# AFE.net
KiCad netlist of a schematic drawn in Altium Designer
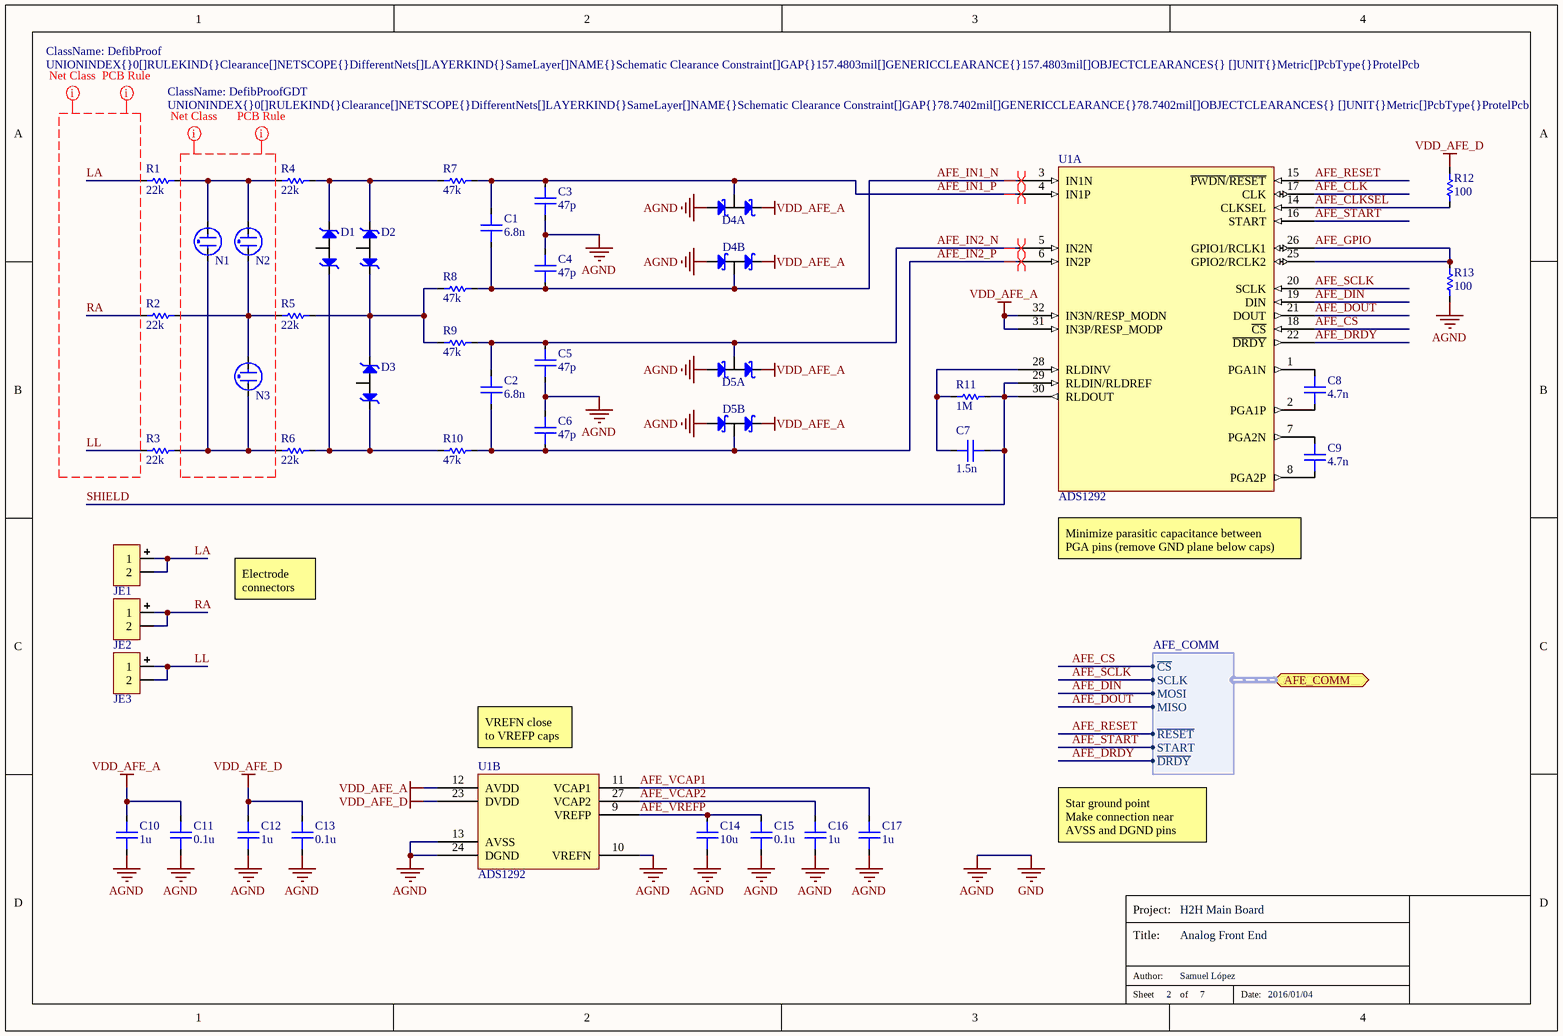
[diagram p0: AFE.SchDoc]

(export (version "E")
  (design (tool "Eeschema 10.0.6"))
  (components
    (comp (ref "C1")
      (value "6.8n")
      (footprint "C0603")
      (description "Capacitor")
      (libsource (lib "Misc") (part "Capacitor"))
    )
    (comp (ref "C2")
      (value "6.8n")
      (footprint "C0603")
      (description "Capacitor")
      (libsource (lib "Misc") (part "Capacitor"))
    )
    (comp (ref "C3")
      (value "47p")
      (footprint "C0603")
      (description "Capacitor")
      (libsource (lib "Misc") (part "Capacitor"))
    )
    (comp (ref "C4")
      (value "47p")
      (footprint "C0603")
      (description "Capacitor")
      (libsource (lib "Misc") (part "Capacitor"))
    )
    (comp (ref "C5")
      (value "47p")
      (footprint "C0603")
      (description "Capacitor")
      (libsource (lib "Misc") (part "Capacitor"))
    )
    (comp (ref "C6")
      (value "47p")
      (footprint "C0603")
      (description "Capacitor")
      (libsource (lib "Misc") (part "Capacitor"))
    )
    (comp (ref "C7")
      (value "1.5n")
      (footprint "C0603")
      (description "Capacitor")
      (libsource (lib "Misc") (part "Capacitor"))
    )
    (comp (ref "C8")
      (value "4.7n")
      (footprint "C0603")
      (description "Capacitor")
      (libsource (lib "Misc") (part "Capacitor"))
    )
    (comp (ref "C9")
      (value "4.7n")
      (footprint "C0603")
      (description "Capacitor")
      (libsource (lib "Misc") (part "Capacitor"))
    )
    (comp (ref "C10")
      (value "1u")
      (footprint "C0603")
      (description "Capacitor")
      (libsource (lib "Misc") (part "Capacitor"))
    )
    (comp (ref "C11")
      (value "0.1u")
      (footprint "C0603")
      (description "Capacitor")
      (libsource (lib "Misc") (part "Capacitor"))
    )
    (comp (ref "C12")
      (value "1u")
      (footprint "C0603")
      (description "Capacitor")
      (libsource (lib "Misc") (part "Capacitor"))
    )
    (comp (ref "C13")
      (value "0.1u")
      (footprint "C0603")
      (description "Capacitor")
      (libsource (lib "Misc") (part "Capacitor"))
    )
    (comp (ref "C14")
      (value "10u")
      (footprint "C0603")
      (description "Capacitor")
      (libsource (lib "Misc") (part "Capacitor"))
    )
    (comp (ref "C15")
      (value "0.1u")
      (footprint "C0603")
      (description "Capacitor")
      (libsource (lib "Misc") (part "Capacitor"))
    )
    (comp (ref "C16")
      (value "1u")
      (footprint "C0603")
      (description "Capacitor")
      (libsource (lib "Misc") (part "Capacitor"))
    )
    (comp (ref "C17")
      (value "1u")
      (footprint "C0603")
      (description "Capacitor")
      (libsource (lib "Misc") (part "Capacitor"))
    )
    (comp (ref "D1")
      (value "PESD5V0X1")
      (footprint "PESD5V0X1BT")
      (description "TVS - Bidirectional Zener Diode")
      (libsource (lib "H2H") (part "PESD5V0X1"))
    )
    (comp (ref "D2")
      (value "PESD5V0X1")
      (footprint "PESD5V0X1BT")
      (description "TVS - Bidirectional Zener Diode")
      (libsource (lib "H2H") (part "PESD5V0X1"))
    )
    (comp (ref "D3")
      (value "PESD5V0X1")
      (footprint "PESD5V0X1BT")
      (description "TVS - Bidirectional Zener Diode")
      (libsource (lib "H2H") (part "PESD5V0X1"))
    )
    (comp (ref "D4")
      (value "BAS70DW-04")
      (footprint "BAS70DW-04")
      (description "TVS - Dual Schottky Rail-to-rail Protection")
      (libsource (lib "H2H") (part "BAS70DW-04"))
    )
    (comp (ref "D5")
      (value "BAS70DW-04")
      (footprint "BAS70DW-04")
      (description "TVS - Dual Schottky Rail-to-rail Protection")
      (libsource (lib "H2H") (part "BAS70DW-04"))
    )
    (comp (ref "JE1")
      (value "JST PH 2 Pin")
      (footprint "S2B-PH-K-S")
      (description "Conn - Battery, Male, 2 Pin, PCB, Right Angle")
      (libsource (lib "Conn") (part "S2B-PH-K-S"))
    )
    (comp (ref "JE2")
      (value "JST PH 2 Pin")
      (footprint "S2B-PH-K-S")
      (description "Conn - Battery, Male, 2 Pin, PCB, Right Angle")
      (libsource (lib "Conn") (part "S2B-PH-K-S"))
    )
    (comp (ref "JE3")
      (value "JST PH 2 Pin")
      (footprint "S2B-PH-K-S")
      (description "Conn - Battery, Male, 2 Pin, PCB, Right Angle")
      (libsource (lib "Conn") (part "S2B-PH-K-S"))
    )
    (comp (ref "N1")
      (value "GDT")
      (footprint "2051-09-SM")
      (description "TVS - Gas Discharge Tube")
      (libsource (lib "H2H") (part "2051-09-SM"))
    )
    (comp (ref "N2")
      (value "GDT")
      (footprint "2051-09-SM")
      (description "TVS - Gas Discharge Tube")
      (libsource (lib "H2H") (part "2051-09-SM"))
    )
    (comp (ref "N3")
      (value "GDT")
      (footprint "2051-09-SM")
      (description "TVS - Gas Discharge Tube")
      (libsource (lib "H2H") (part "2051-09-SM"))
    )
    (comp (ref "R1")
      (value "22k")
      (footprint "R2512")
      (description "Resistor")
      (libsource (lib "Misc") (part "Resistor"))
    )
    (comp (ref "R2")
      (value "22k")
      (footprint "R2512")
      (description "Resistor")
      (libsource (lib "Misc") (part "Resistor"))
    )
    (comp (ref "R3")
      (value "22k")
      (footprint "R2512")
      (description "Resistor")
      (libsource (lib "Misc") (part "Resistor"))
    )
    (comp (ref "R4")
      (value "22k")
      (footprint "R2512")
      (description "Resistor")
      (libsource (lib "Misc") (part "Resistor"))
    )
    (comp (ref "R5")
      (value "22k")
      (footprint "R2512")
      (description "Resistor")
      (libsource (lib "Misc") (part "Resistor"))
    )
    (comp (ref "R6")
      (value "22k")
      (footprint "R2512")
      (description "Resistor")
      (libsource (lib "Misc") (part "Resistor"))
    )
    (comp (ref "R7")
      (value "47k")
      (footprint "R0603")
      (description "Resistor")
      (libsource (lib "Misc") (part "Resistor"))
    )
    (comp (ref "R8")
      (value "47k")
      (footprint "R0603")
      (description "Resistor")
      (libsource (lib "Misc") (part "Resistor"))
    )
    (comp (ref "R9")
      (value "47k")
      (footprint "R0603")
      (description "Resistor")
      (libsource (lib "Misc") (part "Resistor"))
    )
    (comp (ref "R10")
      (value "47k")
      (footprint "R0603")
      (description "Resistor")
      (libsource (lib "Misc") (part "Resistor"))
    )
    (comp (ref "R11")
      (value "1M")
      (footprint "R0603")
      (description "Resistor")
      (libsource (lib "Misc") (part "Resistor"))
    )
    (comp (ref "R12")
      (value "100")
      (footprint "R0603")
      (description "Resistor")
      (libsource (lib "Misc") (part "Resistor"))
    )
    (comp (ref "R13")
      (value "100")
      (footprint "R0603")
      (description "Resistor")
      (libsource (lib "Misc") (part "Resistor"))
    )
    (comp (ref "U1")
      (value "ADS1292")
      (footprint "ADS129x")
      (description "IC - Analog Front End - Medical")
      (libsource (lib "H2H") (part "ADS1292"))
    )
  )
  (nets
    (net (code "2") (name "/AFE_CLK") (class "Default")
      (node (ref "U1") (pin "17") (pinfunction "CLK_17") (pintype "bidirectional"))
    )
    (net (code "3") (name "/AFE_CLKSEL") (class "Default")
      (node (ref "R12") (pin "2") (pinfunction "2_2") (pintype "passive"))
      (node (ref "U1") (pin "14") (pinfunction "CLKSEL_14") (pintype "input"))
    )
    (net (code "4") (name "/AFE_CS") (class "Default")
      (node (ref "U1") (pin "18") (pinfunction "~{CS}_18") (pintype "input"))
    )
    (net (code "5") (name "/AFE_DIN") (class "Default")
      (node (ref "U1") (pin "19") (pinfunction "DIN_19") (pintype "input"))
    )
    (net (code "6") (name "/AFE_DOUT") (class "Default")
      (node (ref "U1") (pin "21") (pinfunction "DOUT_21") (pintype "output"))
    )
    (net (code "7") (name "/AFE_DRDY") (class "Default")
      (node (ref "U1") (pin "22") (pinfunction "~{DRDY}_22") (pintype "output"))
    )
    (net (code "8") (name "/AFE_GPIO") (class "Default")
      (node (ref "R13") (pin "1") (pinfunction "1_1") (pintype "passive"))
      (node (ref "U1") (pin "25") (pinfunction "GPIO2/RCLK2_25") (pintype "bidirectional"))
      (node (ref "U1") (pin "26") (pinfunction "GPIO1/RCLK1_26") (pintype "bidirectional"))
    )
    (net (code "9") (name "/AFE_IN1_N") (class "Default")
      (node (ref "C1") (pin "1") (pinfunction "1_1") (pintype "passive"))
      (node (ref "C4") (pin "1") (pinfunction "1_1") (pintype "passive"))
      (node (ref "D4") (pin "3") (pinfunction "AK2_3") (pintype "passive"))
      (node (ref "R8") (pin "2") (pinfunction "2_2") (pintype "passive"))
      (node (ref "U1") (pin "3") (pinfunction "IN1N_3") (pintype "input"))
    )
    (net (code "10") (name "/AFE_IN1_P") (class "Default")
      (node (ref "C1") (pin "2") (pinfunction "2_2") (pintype "passive"))
      (node (ref "C3") (pin "2") (pinfunction "2_2") (pintype "passive"))
      (node (ref "D4") (pin "6") (pinfunction "AK1_6") (pintype "passive"))
      (node (ref "R7") (pin "2") (pinfunction "2_2") (pintype "passive"))
      (node (ref "U1") (pin "4") (pinfunction "IN1P_4") (pintype "input"))
    )
    (net (code "11") (name "/AFE_IN2_N") (class "Default")
      (node (ref "C2") (pin "2") (pinfunction "2_2") (pintype "passive"))
      (node (ref "C5") (pin "2") (pinfunction "2_2") (pintype "passive"))
      (node (ref "D5") (pin "6") (pinfunction "AK1_6") (pintype "passive"))
      (node (ref "R9") (pin "2") (pinfunction "2_2") (pintype "passive"))
      (node (ref "U1") (pin "5") (pinfunction "IN2N_5") (pintype "input"))
    )
    (net (code "12") (name "/AFE_IN2_P") (class "Default")
      (node (ref "C2") (pin "1") (pinfunction "1_1") (pintype "passive"))
      (node (ref "C6") (pin "1") (pinfunction "1_1") (pintype "passive"))
      (node (ref "D5") (pin "3") (pinfunction "AK2_3") (pintype "passive"))
      (node (ref "R10") (pin "2") (pinfunction "2_2") (pintype "passive"))
      (node (ref "U1") (pin "6") (pinfunction "IN2P_6") (pintype "input"))
    )
    (net (code "13") (name "/AFE_RESET") (class "Default")
      (node (ref "U1") (pin "15") (pinfunction "~{PWDN}/~{RESET}_15") (pintype "input"))
    )
    (net (code "14") (name "/AFE_SCLK") (class "Default")
      (node (ref "U1") (pin "20") (pinfunction "SCLK_20") (pintype "input"))
    )
    (net (code "15") (name "/AFE_START") (class "Default")
      (node (ref "U1") (pin "16") (pinfunction "START_16") (pintype "input"))
    )
    (net (code "16") (name "/AFE_VCAP1") (class "Default")
      (node (ref "C17") (pin "2") (pinfunction "2_2") (pintype "passive"))
      (node (ref "U1") (pin "11") (pinfunction "VCAP1_11") (pintype "passive"))
    )
    (net (code "17") (name "/AFE_VCAP2") (class "Default")
      (node (ref "C16") (pin "2") (pinfunction "2_2") (pintype "passive"))
      (node (ref "U1") (pin "27") (pinfunction "VCAP2_27") (pintype "passive"))
    )
    (net (code "18") (name "/AFE_VREFP") (class "Default")
      (node (ref "C14") (pin "2") (pinfunction "2_2") (pintype "passive"))
      (node (ref "C15") (pin "2") (pinfunction "2_2") (pintype "passive"))
      (node (ref "U1") (pin "9") (pinfunction "VREFP_9") (pintype "passive"))
    )
    (net (code "19") (name "/LA") (class "Default")
      (node (ref "JE1") (pin "1") (pinfunction "1_1") (pintype "passive"))
      (node (ref "JE1") (pin "2") (pinfunction "2_2") (pintype "passive"))
      (node (ref "R1") (pin "1") (pinfunction "1_1") (pintype "passive"))
    )
    (net (code "20") (name "/LL") (class "Default")
      (node (ref "JE3") (pin "1") (pinfunction "1_1") (pintype "passive"))
      (node (ref "JE3") (pin "2") (pinfunction "2_2") (pintype "passive"))
      (node (ref "R3") (pin "1") (pinfunction "1_1") (pintype "passive"))
    )
    (net (code "21") (name "/RA") (class "Default")
      (node (ref "JE2") (pin "1") (pinfunction "1_1") (pintype "passive"))
      (node (ref "JE2") (pin "2") (pinfunction "2_2") (pintype "passive"))
      (node (ref "R2") (pin "1") (pinfunction "1_1") (pintype "passive"))
    )
    (net (code "22") (name "/SHIELD") (class "Default")
      (node (ref "C7") (pin "1") (pinfunction "1_1") (pintype "passive"))
      (node (ref "R11") (pin "2") (pinfunction "2_2") (pintype "passive"))
      (node (ref "U1") (pin "29") (pinfunction "RLDIN/RLDREF_29") (pintype "input"))
      (node (ref "U1") (pin "30") (pinfunction "RLDOUT_30") (pintype "output"))
    )
    (net (code "24") (name "AGND") (class "Default")
      (node (ref "C10") (pin "1") (pinfunction "1_1") (pintype "passive"))
      (node (ref "C11") (pin "1") (pinfunction "1_1") (pintype "passive"))
      (node (ref "C12") (pin "1") (pinfunction "1_1") (pintype "passive"))
      (node (ref "C13") (pin "1") (pinfunction "1_1") (pintype "passive"))
      (node (ref "C14") (pin "1") (pinfunction "1_1") (pintype "passive"))
      (node (ref "C15") (pin "1") (pinfunction "1_1") (pintype "passive"))
      (node (ref "C16") (pin "1") (pinfunction "1_1") (pintype "passive"))
      (node (ref "C17") (pin "1") (pinfunction "1_1") (pintype "passive"))
      (node (ref "C3") (pin "1") (pinfunction "1_1") (pintype "passive"))
      (node (ref "C4") (pin "2") (pinfunction "2_2") (pintype "passive"))
      (node (ref "C5") (pin "1") (pinfunction "1_1") (pintype "passive"))
      (node (ref "C6") (pin "2") (pinfunction "2_2") (pintype "passive"))
      (node (ref "D4") (pin "1") (pinfunction "A1_1") (pintype "passive"))
      (node (ref "D4") (pin "4") (pinfunction "A2_4") (pintype "passive"))
      (node (ref "D5") (pin "1") (pinfunction "A1_1") (pintype "passive"))
      (node (ref "D5") (pin "4") (pinfunction "A2_4") (pintype "passive"))
      (node (ref "R13") (pin "2") (pinfunction "2_2") (pintype "passive"))
      (node (ref "U1") (pin "10") (pinfunction "VREFN_10") (pintype "passive"))
      (node (ref "U1") (pin "13") (pinfunction "AVSS_13") (pintype "power_in"))
      (node (ref "U1") (pin "24") (pinfunction "DGND_24") (pintype "power_in"))
    )
    (net (code "25") (name "Net-(D1-K1)") (class "Default")
      (node (ref "D1") (pin "1") (pinfunction "K1_1") (pintype "passive"))
      (node (ref "D3") (pin "1") (pinfunction "K1_1") (pintype "passive"))
      (node (ref "R10") (pin "1") (pinfunction "1_1") (pintype "passive"))
      (node (ref "R6") (pin "2") (pinfunction "2_2") (pintype "passive"))
    )
    (net (code "26") (name "Net-(D1-K2)") (class "Default")
      (node (ref "D1") (pin "2") (pinfunction "K2_2") (pintype "passive"))
      (node (ref "D2") (pin "2") (pinfunction "K2_2") (pintype "passive"))
      (node (ref "R4") (pin "2") (pinfunction "2_2") (pintype "passive"))
      (node (ref "R7") (pin "1") (pinfunction "1_1") (pintype "passive"))
    )
    (net (code "27") (name "Net-(D2-K1)") (class "Default")
      (node (ref "D2") (pin "1") (pinfunction "K1_1") (pintype "passive"))
      (node (ref "D3") (pin "2") (pinfunction "K2_2") (pintype "passive"))
      (node (ref "R5") (pin "2") (pinfunction "2_2") (pintype "passive"))
      (node (ref "R8") (pin "1") (pinfunction "1_1") (pintype "passive"))
      (node (ref "R9") (pin "1") (pinfunction "1_1") (pintype "passive"))
    )
    (net (code "28") (name "Net-(N1-Pad1)") (class "Default")
      (node (ref "N1") (pin "1") (pinfunction "1_1") (pintype "passive"))
      (node (ref "N3") (pin "1") (pinfunction "1_1") (pintype "passive"))
      (node (ref "R3") (pin "2") (pinfunction "2_2") (pintype "passive"))
      (node (ref "R6") (pin "1") (pinfunction "1_1") (pintype "passive"))
    )
    (net (code "29") (name "Net-(N1-Pad2)") (class "Default")
      (node (ref "N1") (pin "2") (pinfunction "2_2") (pintype "passive"))
      (node (ref "N2") (pin "2") (pinfunction "2_2") (pintype "passive"))
      (node (ref "R1") (pin "2") (pinfunction "2_2") (pintype "passive"))
      (node (ref "R4") (pin "1") (pinfunction "1_1") (pintype "passive"))
    )
    (net (code "30") (name "Net-(N2-Pad1)") (class "Default")
      (node (ref "N2") (pin "1") (pinfunction "1_1") (pintype "passive"))
      (node (ref "N3") (pin "2") (pinfunction "2_2") (pintype "passive"))
      (node (ref "R2") (pin "2") (pinfunction "2_2") (pintype "passive"))
      (node (ref "R5") (pin "1") (pinfunction "1_1") (pintype "passive"))
    )
    (net (code "31") (name "Net-(U1A-PGA1N)") (class "Default")
      (node (ref "C8") (pin "2") (pinfunction "2_2") (pintype "passive"))
      (node (ref "U1") (pin "1") (pinfunction "PGA1N_1") (pintype "output"))
    )
    (net (code "32") (name "Net-(U1A-PGA1P)") (class "Default")
      (node (ref "C8") (pin "1") (pinfunction "1_1") (pintype "passive"))
      (node (ref "U1") (pin "2") (pinfunction "PGA1P_2") (pintype "output"))
    )
    (net (code "33") (name "Net-(U1A-PGA2N)") (class "Default")
      (node (ref "C9") (pin "2") (pinfunction "2_2") (pintype "passive"))
      (node (ref "U1") (pin "7") (pinfunction "PGA2N_7") (pintype "output"))
    )
    (net (code "34") (name "Net-(U1A-PGA2P)") (class "Default")
      (node (ref "C9") (pin "1") (pinfunction "1_1") (pintype "passive"))
      (node (ref "U1") (pin "8") (pinfunction "PGA2P_8") (pintype "output"))
    )
    (net (code "35") (name "Net-(U1A-RLDINV)") (class "Default")
      (node (ref "C7") (pin "2") (pinfunction "2_2") (pintype "passive"))
      (node (ref "R11") (pin "1") (pinfunction "1_1") (pintype "passive"))
      (node (ref "U1") (pin "28") (pinfunction "RLDINV_28") (pintype "input"))
    )
    (net (code "36") (name "VDD_AFE_A") (class "Default")
      (node (ref "C10") (pin "2") (pinfunction "2_2") (pintype "passive"))
      (node (ref "C11") (pin "2") (pinfunction "2_2") (pintype "passive"))
      (node (ref "D4") (pin "2") (pinfunction "K1_2") (pintype "passive"))
      (node (ref "D4") (pin "5") (pinfunction "K2_5") (pintype "passive"))
      (node (ref "D5") (pin "2") (pinfunction "K1_2") (pintype "passive"))
      (node (ref "D5") (pin "5") (pinfunction "K2_5") (pintype "passive"))
      (node (ref "U1") (pin "12") (pinfunction "AVDD_12") (pintype "power_in"))
      (node (ref "U1") (pin "31") (pinfunction "IN3P/RESP_MODP_31") (pintype "input"))
      (node (ref "U1") (pin "32") (pinfunction "IN3N/RESP_MODN_32") (pintype "input"))
    )
    (net (code "37") (name "VDD_AFE_D") (class "Default")
      (node (ref "C12") (pin "2") (pinfunction "2_2") (pintype "passive"))
      (node (ref "C13") (pin "2") (pinfunction "2_2") (pintype "passive"))
      (node (ref "R12") (pin "1") (pinfunction "1_1") (pintype "passive"))
      (node (ref "U1") (pin "23") (pinfunction "DVDD_23") (pintype "power_in"))
    )
    (net (code "38") (name "unconnected-(D1-A-Pad3)") (class "Default")
      (node (ref "D1") (pin "3") (pinfunction "A_3") (pintype "passive"))
    )
    (net (code "39") (name "unconnected-(D2-A-Pad3)") (class "Default")
      (node (ref "D2") (pin "3") (pinfunction "A_3") (pintype "passive"))
    )
    (net (code "40") (name "unconnected-(D3-A-Pad3)") (class "Default")
      (node (ref "D3") (pin "3") (pinfunction "A_3") (pintype "passive"))
    )
  )
)
